# Soil_Moisture_Sensor.net
KiCad netlist of a schematic drawn in Altium Designer
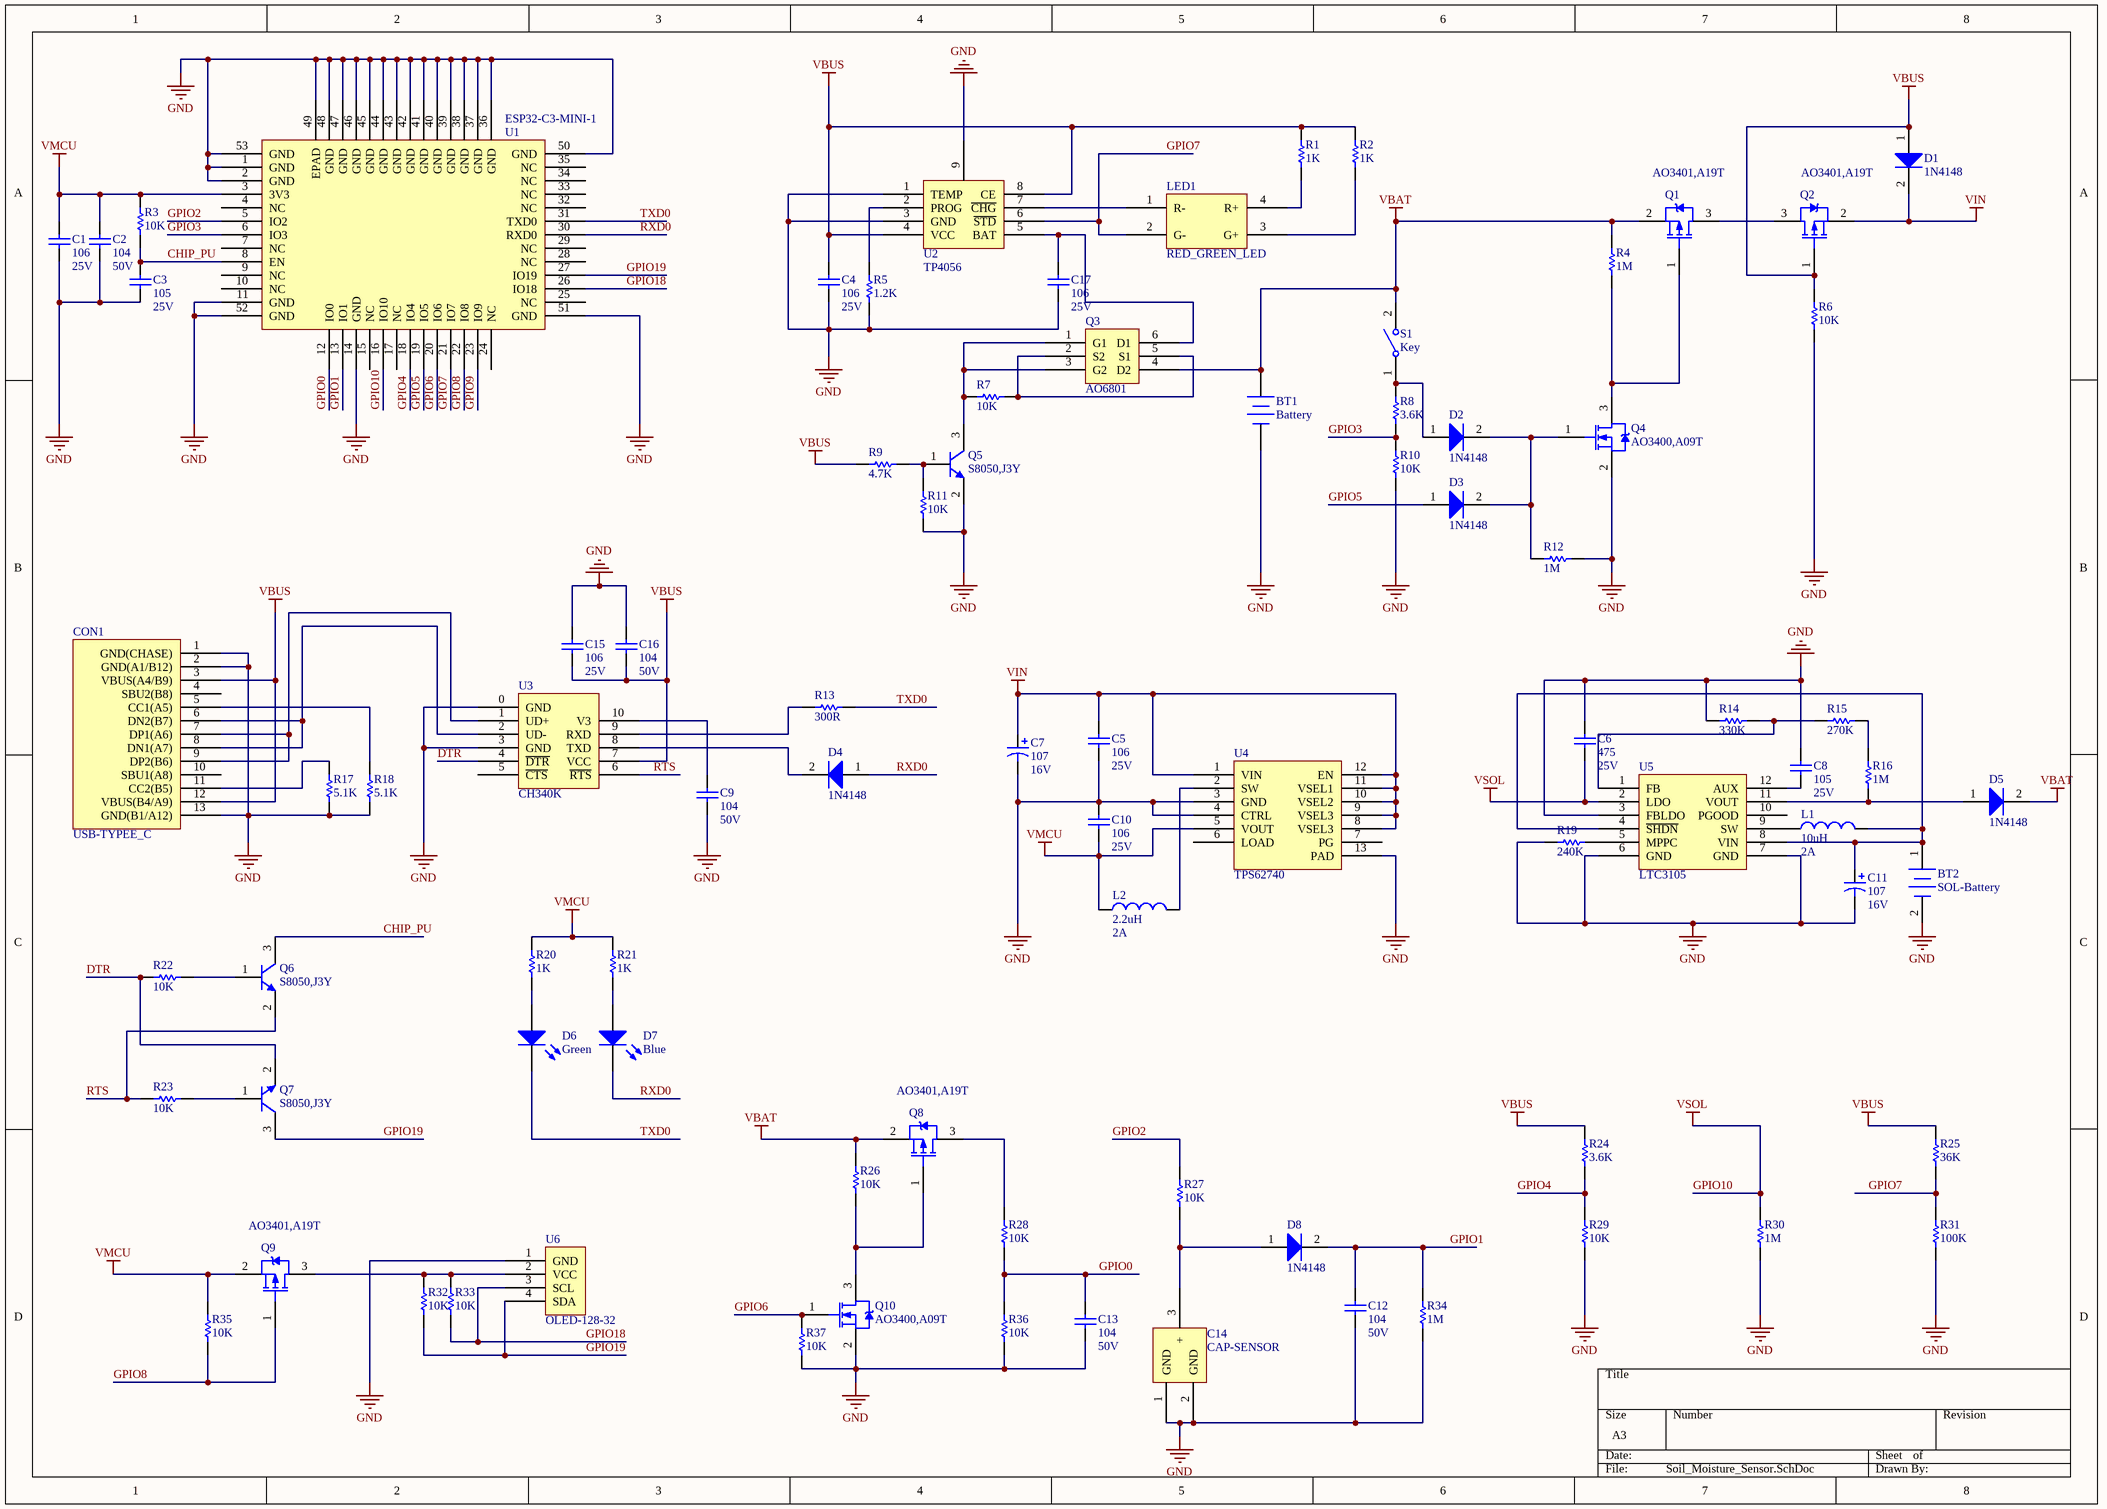
[diagram p0: Soil_Moisture_Sensor.SchDoc]

(export (version "E")
  (design (tool "Eeschema 10.0.6"))
  (components
    (comp (ref "BT1")
      (value "Battery")
      (footprint "Soil_Moisture_Sensor:BATTERY")
      (description "Multicell Battery")
      (fields (field (name "PUBLISHER") "Altium Limited"))
      (libsource (lib "") (part "Battery_1"))
    )
    (comp (ref "BT2")
      (value "SOL-Battery")
      (footprint "Soil_Moisture_Sensor:BATTERY-SOL")
      (description "Multicell Battery")
      (fields (field (name "PUBLISHER") "Altium Limited"))
      (libsource (lib "Miscellaneous Devices") (part "Battery"))
    )
    (comp (ref "C1")
      (value "25V")
      (footprint "Soil_Moisture_Sensor:CAPC1608L")
      (description "Capacitor")
      (fields (field (name "ALTIUM_VALUE") "106") (field (name "PUBLISHER") "Altium Limited"))
      (libsource (lib "Miscellaneous Devices") (part "Cap"))
    )
    (comp (ref "C2")
      (value "50V")
      (footprint "Soil_Moisture_Sensor:CAPC1608L")
      (description "Capacitor")
      (fields (field (name "ALTIUM_VALUE") "104") (field (name "PUBLISHER") "Altium Limited"))
      (libsource (lib "Miscellaneous Devices") (part "Cap"))
    )
    (comp (ref "C3")
      (value "25V")
      (footprint "Soil_Moisture_Sensor:CAPC1608L")
      (description "Capacitor")
      (fields (field (name "ALTIUM_VALUE") "105") (field (name "PUBLISHER") "Altium Limited"))
      (libsource (lib "Miscellaneous Devices") (part "Cap"))
    )
    (comp (ref "C4")
      (value "25V")
      (footprint "Soil_Moisture_Sensor:CAPC1608L")
      (description "Capacitor")
      (fields (field (name "ALTIUM_VALUE") "106") (field (name "PUBLISHER") "Altium Limited"))
      (libsource (lib "Miscellaneous Devices") (part "Cap"))
    )
    (comp (ref "C5")
      (value "25V")
      (footprint "Soil_Moisture_Sensor:CAPC1608L")
      (description "Capacitor")
      (fields (field (name "ALTIUM_VALUE") "106") (field (name "PUBLISHER") "Altium Limited"))
      (libsource (lib "Miscellaneous Devices") (part "Cap"))
    )
    (comp (ref "C6")
      (value "25V")
      (footprint "Soil_Moisture_Sensor:CAPC1608L")
      (description "Capacitor")
      (fields (field (name "ALTIUM_VALUE") "475") (field (name "PUBLISHER") "Altium Limited"))
      (libsource (lib "Miscellaneous Devices") (part "Cap"))
    )
    (comp (ref "C7")
      (value "16V")
      (footprint "Soil_Moisture_Sensor:TC6032-2412")
      (description "Polarized Capacitor (Radial)")
      (fields (field (name "ALTIUM_VALUE") "107") (field (name "PUBLISHER") "Altium Limited"))
      (libsource (lib "Miscellaneous Devices") (part "Cap Pol1"))
    )
    (comp (ref "C8")
      (value "25V")
      (footprint "Soil_Moisture_Sensor:CAPC1608L")
      (description "Capacitor")
      (fields (field (name "ALTIUM_VALUE") "105") (field (name "PUBLISHER") "Altium Limited"))
      (libsource (lib "Miscellaneous Devices") (part "Cap"))
    )
    (comp (ref "C9")
      (value "50V")
      (footprint "Soil_Moisture_Sensor:CAPC1608L")
      (description "Capacitor")
      (fields (field (name "ALTIUM_VALUE") "104") (field (name "PUBLISHER") "Altium Limited"))
      (libsource (lib "Miscellaneous Devices") (part "Cap"))
    )
    (comp (ref "C10")
      (value "25V")
      (footprint "Soil_Moisture_Sensor:CAPC1608L")
      (description "Capacitor")
      (fields (field (name "ALTIUM_VALUE") "106") (field (name "PUBLISHER") "Altium Limited"))
      (libsource (lib "Miscellaneous Devices") (part "Cap"))
    )
    (comp (ref "C11")
      (value "16V")
      (footprint "Soil_Moisture_Sensor:TC6032-2412")
      (description "Polarized Capacitor (Radial)")
      (fields (field (name "ALTIUM_VALUE") "107") (field (name "PUBLISHER") "Altium Limited"))
      (libsource (lib "Miscellaneous Devices") (part "Cap Pol1"))
    )
    (comp (ref "C12")
      (value "50V")
      (footprint "Soil_Moisture_Sensor:CAPC1608L")
      (description "Capacitor")
      (fields (field (name "ALTIUM_VALUE") "104") (field (name "PUBLISHER") "Altium Limited"))
      (libsource (lib "Miscellaneous Devices") (part "Cap"))
    )
    (comp (ref "C13")
      (value "50V")
      (footprint "Soil_Moisture_Sensor:CAPC1608L")
      (description "Capacitor")
      (fields (field (name "ALTIUM_VALUE") "104") (field (name "PUBLISHER") "Altium Limited"))
      (libsource (lib "Miscellaneous Devices") (part "Cap"))
    )
    (comp (ref "C14")
      (value "CAP-SENSOR")
      (footprint "CAP-SENSOR")
      (libsource (lib "Soil_Moisture_Sensor") (part "CAP-SENSOR"))
    )
    (comp (ref "C15")
      (value "25V")
      (footprint "Soil_Moisture_Sensor:CAPC1608L")
      (description "Capacitor")
      (fields (field (name "ALTIUM_VALUE") "106") (field (name "PUBLISHER") "Altium Limited"))
      (libsource (lib "Miscellaneous Devices") (part "Cap"))
    )
    (comp (ref "C16")
      (value "50V")
      (footprint "Soil_Moisture_Sensor:CAPC1608L")
      (description "Capacitor")
      (fields (field (name "ALTIUM_VALUE") "104") (field (name "PUBLISHER") "Altium Limited"))
      (libsource (lib "Miscellaneous Devices") (part "Cap"))
    )
    (comp (ref "C17")
      (value "25V")
      (footprint "Soil_Moisture_Sensor:CAPC1608L")
      (description "Capacitor")
      (fields (field (name "ALTIUM_VALUE") "106") (field (name "PUBLISHER") "Altium Limited"))
      (libsource (lib "Miscellaneous Devices") (part "Cap"))
    )
    (comp (ref "CON1")
      (value "USB-TYPEE_C")
      (footprint "Soil_Moisture_Sensor:USB-TYPE_C")
      (libsource (lib "Soil_Moisture_Sensor") (part "USB-TYPEE_C"))
    )
    (comp (ref "D1")
      (value "1N4148")
      (footprint "Soil_Moisture_Sensor:CD3216-1206")
      (description "Default Diode")
      (fields (field (name "PUBLISHER") "Altium Limited"))
      (libsource (lib "Miscellaneous Devices") (part "Diode"))
    )
    (comp (ref "D2")
      (value "1N4148")
      (footprint "Soil_Moisture_Sensor:CD3216-1206")
      (description "Default Diode")
      (fields (field (name "PUBLISHER") "Altium Limited"))
      (libsource (lib "Miscellaneous Devices") (part "Diode"))
    )
    (comp (ref "D3")
      (value "1N4148")
      (footprint "Soil_Moisture_Sensor:CD3216-1206")
      (description "Default Diode")
      (fields (field (name "PUBLISHER") "Altium Limited"))
      (libsource (lib "Miscellaneous Devices") (part "Diode"))
    )
    (comp (ref "D4")
      (value "1N4148")
      (footprint "Soil_Moisture_Sensor:CD3216-1206")
      (description "Default Diode")
      (fields (field (name "PUBLISHER") "Altium Limited"))
      (libsource (lib "Miscellaneous Devices") (part "Diode"))
    )
    (comp (ref "D5")
      (value "1N4148")
      (footprint "Soil_Moisture_Sensor:CD3216-1206")
      (description "Default Diode")
      (fields (field (name "PUBLISHER") "Altium Limited"))
      (libsource (lib "Miscellaneous Devices") (part "Diode"))
    )
    (comp (ref "D6")
      (value "Green")
      (footprint "Soil_Moisture_Sensor:CD1608-0603")
      (description "Typical INFRARED GaAs LED")
      (fields (field (name "PUBLISHER") "Altium Limited"))
      (libsource (lib "Miscellaneous Devices") (part "LED0"))
    )
    (comp (ref "D7")
      (value "Blue")
      (footprint "Soil_Moisture_Sensor:CD1608-0603")
      (description "Typical INFRARED GaAs LED")
      (fields (field (name "PUBLISHER") "Altium Limited"))
      (libsource (lib "Miscellaneous Devices") (part "LED0"))
    )
    (comp (ref "D8")
      (value "1N4148")
      (footprint "Soil_Moisture_Sensor:CD3216-1206")
      (description "Default Diode")
      (fields (field (name "PUBLISHER") "Altium Limited"))
      (libsource (lib "Miscellaneous Devices") (part "Diode"))
    )
    (comp (ref "L1")
      (value "2A")
      (footprint "Soil_Moisture_Sensor:INDC2520X06N")
      (description "Inductor")
      (fields (field (name "ALTIUM_VALUE") "10uH") (field (name "PUBLISHER") "Altium Limited"))
      (libsource (lib "Miscellaneous Devices") (part "Inductor"))
    )
    (comp (ref "L2")
      (value "2A")
      (footprint "Soil_Moisture_Sensor:INDC2520X06N")
      (description "Inductor")
      (fields (field (name "ALTIUM_VALUE") "2.2uH") (field (name "PUBLISHER") "Altium Limited"))
      (libsource (lib "Miscellaneous Devices") (part "Inductor"))
    )
    (comp (ref "LED1")
      (value "RED_GREEN_LED")
      (footprint "Soil_Moisture_Sensor:RED_GREEN_LED1206")
      (libsource (lib "Soil_Moisture_Sensor") (part "RED_GREEN_LED"))
    )
    (comp (ref "Q1")
      (value "AO3401,A19T")
      (footprint "Soil_Moisture_Sensor:SOT-23B_L")
      (description "P-Channel Power MOSFET")
      (fields (field (name "PUBLISHER") "Altium Limited"))
      (libsource (lib "Miscellaneous Devices") (part "PMOS-2"))
    )
    (comp (ref "Q2")
      (value "AO3401,A19T")
      (footprint "Soil_Moisture_Sensor:SOT-23B_L")
      (description "P-Channel Power MOSFET")
      (fields (field (name "PUBLISHER") "Altium Limited"))
      (libsource (lib "Miscellaneous Devices") (part "PMOS-2"))
    )
    (comp (ref "Q3")
      (value "AO6801")
      (footprint "Soil_Moisture_Sensor:SOT95P330-6M")
      (libsource (lib "FireFly") (part "AO6801"))
    )
    (comp (ref "Q4")
      (value "AO3400,A09T")
      (footprint "Soil_Moisture_Sensor:SOT-23B_L")
      (description "N-Channel Power MOSFET")
      (fields (field (name "PUBLISHER") "Altium Limited"))
      (libsource (lib "Miscellaneous Devices") (part "NMOS-2"))
    )
    (comp (ref "Q5")
      (value "S8050,J3Y")
      (footprint "Soil_Moisture_Sensor:SOT-23B_L")
      (description "NPN Bipolar Transistor")
      (fields (field (name "PUBLISHER") "Altium Limited"))
      (libsource (lib "Miscellaneous Devices") (part "NPN"))
    )
    (comp (ref "Q6")
      (value "S8050,J3Y")
      (footprint "Soil_Moisture_Sensor:SOT-23B_L")
      (description "NPN Bipolar Transistor")
      (fields (field (name "PUBLISHER") "Altium Limited"))
      (libsource (lib "Miscellaneous Devices") (part "NPN"))
    )
    (comp (ref "Q7")
      (value "S8050,J3Y")
      (footprint "Soil_Moisture_Sensor:SOT-23B_L")
      (description "NPN Bipolar Transistor")
      (fields (field (name "PUBLISHER") "Altium Limited"))
      (libsource (lib "Miscellaneous Devices") (part "NPN"))
    )
    (comp (ref "Q8")
      (value "AO3401,A19T")
      (footprint "Soil_Moisture_Sensor:SOT-23B_L")
      (description "P-Channel Power MOSFET")
      (fields (field (name "PUBLISHER") "Altium Limited"))
      (libsource (lib "Miscellaneous Devices") (part "PMOS-2"))
    )
    (comp (ref "Q9")
      (value "AO3401,A19T")
      (footprint "Soil_Moisture_Sensor:SOT-23B_L")
      (description "P-Channel Power MOSFET")
      (fields (field (name "PUBLISHER") "Altium Limited"))
      (libsource (lib "Miscellaneous Devices") (part "PMOS-2"))
    )
    (comp (ref "Q10")
      (value "AO3400,A09T")
      (footprint "Soil_Moisture_Sensor:SOT-23B_L")
      (description "N-Channel Power MOSFET")
      (fields (field (name "PUBLISHER") "Altium Limited"))
      (libsource (lib "Miscellaneous Devices") (part "NMOS-2"))
    )
    (comp (ref "R1")
      (value "1K")
      (footprint "Soil_Moisture_Sensor:RESC1608L")
      (description "Resistor")
      (fields (field (name "Comment") "Res1") (field (name "PUBLISHER") "Altium Limited"))
      (libsource (lib "Miscellaneous Devices") (part "Res1"))
    )
    (comp (ref "R2")
      (value "1K")
      (footprint "Soil_Moisture_Sensor:RESC1608L")
      (description "Resistor")
      (fields (field (name "Comment") "Res1") (field (name "PUBLISHER") "Altium Limited"))
      (libsource (lib "Miscellaneous Devices") (part "Res1"))
    )
    (comp (ref "R3")
      (value "10K")
      (footprint "Soil_Moisture_Sensor:RESC1608L")
      (description "Resistor")
      (fields (field (name "Comment") "Res1") (field (name "PUBLISHER") "Altium Limited"))
      (libsource (lib "Miscellaneous Devices") (part "Res1"))
    )
    (comp (ref "R4")
      (value "1M")
      (footprint "Soil_Moisture_Sensor:RESC1608L")
      (description "Resistor")
      (fields (field (name "Comment") "Res1") (field (name "PUBLISHER") "Altium Limited"))
      (libsource (lib "Miscellaneous Devices") (part "Res1"))
    )
    (comp (ref "R5")
      (value "1.2K")
      (footprint "Soil_Moisture_Sensor:RESC1608L")
      (description "Resistor")
      (fields (field (name "Comment") "Res1") (field (name "PUBLISHER") "Altium Limited"))
      (libsource (lib "Miscellaneous Devices") (part "Res1"))
    )
    (comp (ref "R6")
      (value "10K")
      (footprint "Soil_Moisture_Sensor:RESC1608L")
      (description "Resistor")
      (fields (field (name "Comment") "Res1") (field (name "PUBLISHER") "Altium Limited"))
      (libsource (lib "Miscellaneous Devices") (part "Res1"))
    )
    (comp (ref "R7")
      (value "10K")
      (footprint "Soil_Moisture_Sensor:RESC1608L")
      (description "Resistor")
      (fields (field (name "Comment") "Res1") (field (name "PUBLISHER") "Altium Limited"))
      (libsource (lib "Miscellaneous Devices") (part "Res1"))
    )
    (comp (ref "R8")
      (value "3.6K")
      (footprint "Soil_Moisture_Sensor:RESC1608L")
      (description "Resistor")
      (fields (field (name "Comment") "Res1") (field (name "PUBLISHER") "Altium Limited"))
      (libsource (lib "Miscellaneous Devices") (part "Res1"))
    )
    (comp (ref "R9")
      (value "4.7K")
      (footprint "Soil_Moisture_Sensor:RESC1608L")
      (description "Resistor")
      (fields (field (name "Comment") "Res1") (field (name "PUBLISHER") "Altium Limited"))
      (libsource (lib "Miscellaneous Devices") (part "Res1"))
    )
    (comp (ref "R10")
      (value "10K")
      (footprint "Soil_Moisture_Sensor:RESC1608L")
      (description "Resistor")
      (fields (field (name "Comment") "Res1") (field (name "PUBLISHER") "Altium Limited"))
      (libsource (lib "Miscellaneous Devices") (part "Res1"))
    )
    (comp (ref "R11")
      (value "10K")
      (footprint "Soil_Moisture_Sensor:RESC1608L")
      (description "Resistor")
      (fields (field (name "Comment") "Res1") (field (name "PUBLISHER") "Altium Limited"))
      (libsource (lib "Miscellaneous Devices") (part "Res1"))
    )
    (comp (ref "R12")
      (value "1M")
      (footprint "Soil_Moisture_Sensor:RESC1608L")
      (description "Resistor")
      (fields (field (name "Comment") "Res1") (field (name "PUBLISHER") "Altium Limited"))
      (libsource (lib "Miscellaneous Devices") (part "Res1"))
    )
    (comp (ref "R13")
      (value "300R")
      (footprint "Soil_Moisture_Sensor:RESC1608L")
      (description "Resistor")
      (fields (field (name "Comment") "Res1") (field (name "PUBLISHER") "Altium Limited"))
      (libsource (lib "Miscellaneous Devices") (part "Res1"))
    )
    (comp (ref "R14")
      (value "330K")
      (footprint "Soil_Moisture_Sensor:RESC1608L")
      (description "Resistor")
      (fields (field (name "Comment") "Res1") (field (name "PUBLISHER") "Altium Limited"))
      (libsource (lib "Miscellaneous Devices") (part "Res1"))
    )
    (comp (ref "R15")
      (value "270K")
      (footprint "Soil_Moisture_Sensor:RESC1608L")
      (description "Resistor")
      (fields (field (name "Comment") "Res1") (field (name "PUBLISHER") "Altium Limited"))
      (libsource (lib "Miscellaneous Devices") (part "Res1"))
    )
    (comp (ref "R16")
      (value "1M")
      (footprint "Soil_Moisture_Sensor:RESC1608L")
      (description "Resistor")
      (fields (field (name "Comment") "Res1") (field (name "PUBLISHER") "Altium Limited"))
      (libsource (lib "Miscellaneous Devices") (part "Res1"))
    )
    (comp (ref "R17")
      (value "5.1K")
      (footprint "Soil_Moisture_Sensor:RESC1608L")
      (description "Resistor")
      (fields (field (name "Comment") "Res1") (field (name "PUBLISHER") "Altium Limited"))
      (libsource (lib "Miscellaneous Devices") (part "Res1"))
    )
    (comp (ref "R18")
      (value "5.1K")
      (footprint "Soil_Moisture_Sensor:RESC1608L")
      (description "Resistor")
      (fields (field (name "Comment") "Res1") (field (name "PUBLISHER") "Altium Limited"))
      (libsource (lib "Miscellaneous Devices") (part "Res1"))
    )
    (comp (ref "R19")
      (value "240K")
      (footprint "Soil_Moisture_Sensor:RESC1608L")
      (description "Resistor")
      (fields (field (name "Comment") "Res1") (field (name "PUBLISHER") "Altium Limited"))
      (libsource (lib "Miscellaneous Devices") (part "Res1"))
    )
    (comp (ref "R20")
      (value "1K")
      (footprint "Soil_Moisture_Sensor:RESC1608L")
      (description "Resistor")
      (fields (field (name "Comment") "Res1") (field (name "PUBLISHER") "Altium Limited"))
      (libsource (lib "Miscellaneous Devices") (part "Res1"))
    )
    (comp (ref "R21")
      (value "1K")
      (footprint "Soil_Moisture_Sensor:RESC1608L")
      (description "Resistor")
      (fields (field (name "Comment") "Res1") (field (name "PUBLISHER") "Altium Limited"))
      (libsource (lib "Miscellaneous Devices") (part "Res1"))
    )
    (comp (ref "R22")
      (value "10K")
      (footprint "Soil_Moisture_Sensor:RESC1608L")
      (description "Resistor")
      (fields (field (name "Comment") "Res1") (field (name "PUBLISHER") "Altium Limited"))
      (libsource (lib "Miscellaneous Devices") (part "Res1"))
    )
    (comp (ref "R23")
      (value "10K")
      (footprint "Soil_Moisture_Sensor:RESC1608L")
      (description "Resistor")
      (fields (field (name "Comment") "Res1") (field (name "PUBLISHER") "Altium Limited"))
      (libsource (lib "Miscellaneous Devices") (part "Res1"))
    )
    (comp (ref "R24")
      (value "3.6K")
      (footprint "Soil_Moisture_Sensor:RESC1608L")
      (description "Resistor")
      (fields (field (name "Comment") "Res1") (field (name "PUBLISHER") "Altium Limited"))
      (libsource (lib "Miscellaneous Devices") (part "Res1"))
    )
    (comp (ref "R25")
      (value "36K")
      (footprint "Soil_Moisture_Sensor:RESC1608L")
      (description "Resistor")
      (fields (field (name "Comment") "Res1") (field (name "PUBLISHER") "Altium Limited"))
      (libsource (lib "Miscellaneous Devices") (part "Res1"))
    )
    (comp (ref "R26")
      (value "10K")
      (footprint "Soil_Moisture_Sensor:RESC1608L")
      (description "Resistor")
      (fields (field (name "Comment") "Res1") (field (name "PUBLISHER") "Altium Limited"))
      (libsource (lib "Miscellaneous Devices") (part "Res1"))
    )
    (comp (ref "R27")
      (value "10K")
      (footprint "Soil_Moisture_Sensor:RESC1608L")
      (description "Resistor")
      (fields (field (name "Comment") "Res1") (field (name "PUBLISHER") "Altium Limited"))
      (libsource (lib "Miscellaneous Devices") (part "Res1"))
    )
    (comp (ref "R28")
      (value "10K")
      (footprint "Soil_Moisture_Sensor:RESC1608L")
      (description "Resistor")
      (fields (field (name "Comment") "Res1") (field (name "PUBLISHER") "Altium Limited"))
      (libsource (lib "Miscellaneous Devices") (part "Res1"))
    )
    (comp (ref "R29")
      (value "10K")
      (footprint "Soil_Moisture_Sensor:RESC1608L")
      (description "Resistor")
      (fields (field (name "Comment") "Res1") (field (name "PUBLISHER") "Altium Limited"))
      (libsource (lib "Miscellaneous Devices") (part "Res1"))
    )
    (comp (ref "R30")
      (value "1M")
      (footprint "Soil_Moisture_Sensor:RESC1608L")
      (description "Resistor")
      (fields (field (name "Comment") "Res1") (field (name "PUBLISHER") "Altium Limited"))
      (libsource (lib "Miscellaneous Devices") (part "Res1"))
    )
    (comp (ref "R31")
      (value "100K")
      (footprint "Soil_Moisture_Sensor:RESC1608L")
      (description "Resistor")
      (fields (field (name "Comment") "Res1") (field (name "PUBLISHER") "Altium Limited"))
      (libsource (lib "Miscellaneous Devices") (part "Res1"))
    )
    (comp (ref "R32")
      (value "10K")
      (footprint "Soil_Moisture_Sensor:RESC1608L")
      (description "Resistor")
      (fields (field (name "Comment") "Res1") (field (name "PUBLISHER") "Altium Limited"))
      (libsource (lib "Miscellaneous Devices") (part "Res1"))
    )
    (comp (ref "R33")
      (value "10K")
      (footprint "Soil_Moisture_Sensor:RESC1608L")
      (description "Resistor")
      (fields (field (name "Comment") "Res1") (field (name "PUBLISHER") "Altium Limited"))
      (libsource (lib "Miscellaneous Devices") (part "Res1"))
    )
    (comp (ref "R34")
      (value "1M")
      (footprint "Soil_Moisture_Sensor:RESC1608L")
      (description "Resistor")
      (fields (field (name "Comment") "Res1") (field (name "PUBLISHER") "Altium Limited"))
      (libsource (lib "Miscellaneous Devices") (part "Res1"))
    )
    (comp (ref "R35")
      (value "10K")
      (footprint "Soil_Moisture_Sensor:RESC1608L")
      (description "Resistor")
      (fields (field (name "Comment") "Res1") (field (name "PUBLISHER") "Altium Limited"))
      (libsource (lib "Miscellaneous Devices") (part "Res1"))
    )
    (comp (ref "R36")
      (value "10K")
      (footprint "Soil_Moisture_Sensor:RESC1608L")
      (description "Resistor")
      (fields (field (name "Comment") "Res1") (field (name "PUBLISHER") "Altium Limited"))
      (libsource (lib "Miscellaneous Devices") (part "Res1"))
    )
    (comp (ref "R37")
      (value "10K")
      (footprint "Soil_Moisture_Sensor:RESC1608L")
      (description "Resistor")
      (fields (field (name "Comment") "Res1") (field (name "PUBLISHER") "Altium Limited"))
      (libsource (lib "Miscellaneous Devices") (part "Res1"))
    )
    (comp (ref "S1")
      (value "Key")
      (footprint "Soil_Moisture_Sensor:KEY")
      (description "Single-Pole, Single-Throw Switch")
      (fields (field (name "PUBLISHER") "Altium Limited"))
      (libsource (lib "Miscellaneous Devices") (part "SW-SPST"))
    )
    (comp (ref "U1")
      (value "ESP32-C3-MINI-1")
      (footprint "Soil_Moisture_Sensor:XCVR_ESP32-C3-MINI-1-N4")
      (libsource (lib "Soil_Moisture_Sensor") (part "ESP32-C3-MINI-1"))
    )
    (comp (ref "U2")
      (value "TP4056")
      (footprint "Soil_Moisture_Sensor:SOP127P780-8M")
      (libsource (lib "Soil_Moisture_Sensor") (part "TP4056"))
    )
    (comp (ref "U3")
      (value "CH340K")
      (footprint "Soil_Moisture_Sensor:ESOP100-10")
      (libsource (lib "Soil_Moisture_Sensor") (part "CH340K"))
    )
    (comp (ref "U4")
      (value "TPS62740")
      (footprint "Soil_Moisture_Sensor:DSS0012A")
      (libsource (lib "Soil_Moisture_Sensor") (part "TPS62740"))
    )
    (comp (ref "U5")
      (value "LTC3105")
      (footprint "Soil_Moisture_Sensor:TSOP65P490X110-12L")
      (libsource (lib "Soil_Moisture_Sensor") (part "LTC3105"))
    )
    (comp (ref "U6")
      (value "OLED-128-32")
      (footprint "OLED-128-32")
      (libsource (lib "Soil_Moisture_Sensor") (part "OLED-128-32"))
    )
  )
  (nets
    (net (code "1") (name "/CHIP_PU") (class "Default")
      (node (ref "C3") (pin "2") (pinfunction "2_2") (pintype "passive"))
      (node (ref "Q6") (pin "3") (pinfunction "C_3") (pintype "passive"))
      (node (ref "R3") (pin "1") (pinfunction "1_1") (pintype "passive"))
      (node (ref "U1") (pin "8") (pinfunction "EN_8") (pintype "passive"))
    )
    (net (code "2") (name "/DTR") (class "Default")
      (node (ref "Q7") (pin "2") (pinfunction "E_2") (pintype "passive"))
      (node (ref "R22") (pin "2") (pinfunction "2_2") (pintype "passive"))
      (node (ref "U3") (pin "4") (pinfunction "~{DTR}_4") (pintype "passive"))
    )
    (net (code "3") (name "/GPIO0") (class "Default")
      (node (ref "C13") (pin "2") (pinfunction "2_2") (pintype "passive"))
      (node (ref "R28") (pin "1") (pinfunction "1_1") (pintype "passive"))
      (node (ref "R36") (pin "2") (pinfunction "2_2") (pintype "passive"))
      (node (ref "U1") (pin "12") (pinfunction "IO0_12") (pintype "passive"))
    )
    (net (code "4") (name "/GPIO1") (class "Default")
      (node (ref "C12") (pin "2") (pinfunction "2_2") (pintype "passive"))
      (node (ref "D8") (pin "2") (pinfunction "K_2") (pintype "passive"))
      (node (ref "R34") (pin "2") (pinfunction "2_2") (pintype "passive"))
      (node (ref "U1") (pin "13") (pinfunction "IO1_13") (pintype "passive"))
    )
    (net (code "5") (name "/GPIO2") (class "Default")
      (node (ref "R27") (pin "2") (pinfunction "2_2") (pintype "passive"))
      (node (ref "U1") (pin "5") (pinfunction "IO2_5") (pintype "passive"))
    )
    (net (code "6") (name "/GPIO3") (class "Default")
      (node (ref "R10") (pin "2") (pinfunction "2_2") (pintype "passive"))
      (node (ref "R8") (pin "1") (pinfunction "1_1") (pintype "passive"))
      (node (ref "U1") (pin "6") (pinfunction "IO3_6") (pintype "passive"))
    )
    (net (code "7") (name "/GPIO4") (class "Default")
      (node (ref "R24") (pin "1") (pinfunction "1_1") (pintype "passive"))
      (node (ref "R29") (pin "2") (pinfunction "2_2") (pintype "passive"))
      (node (ref "U1") (pin "18") (pinfunction "IO4_18") (pintype "passive"))
    )
    (net (code "8") (name "/GPIO5") (class "Default")
      (node (ref "D3") (pin "1") (pinfunction "A_1") (pintype "passive"))
      (node (ref "U1") (pin "19") (pinfunction "IO5_19") (pintype "passive"))
    )
    (net (code "9") (name "/GPIO6") (class "Default")
      (node (ref "Q10") (pin "1") (pinfunction "G_1") (pintype "passive"))
      (node (ref "R37") (pin "2") (pinfunction "2_2") (pintype "passive"))
      (node (ref "U1") (pin "20") (pinfunction "IO6_20") (pintype "passive"))
    )
    (net (code "10") (name "/GPIO7") (class "Default")
      (node (ref "LED1") (pin "2") (pinfunction "G-_2") (pintype "passive"))
      (node (ref "R25") (pin "1") (pinfunction "1_1") (pintype "passive"))
      (node (ref "R31") (pin "2") (pinfunction "2_2") (pintype "passive"))
      (node (ref "U1") (pin "21") (pinfunction "IO7_21") (pintype "passive"))
      (node (ref "U2") (pin "6") (pinfunction "~{STD}_6") (pintype "passive"))
    )
    (net (code "11") (name "/GPIO8") (class "Default")
      (node (ref "Q9") (pin "1") (pinfunction "G_1") (pintype "passive"))
      (node (ref "R35") (pin "1") (pinfunction "1_1") (pintype "passive"))
      (node (ref "U1") (pin "22") (pinfunction "IO8_22") (pintype "passive"))
    )
    (net (code "12") (name "/GPIO9") (class "Default")
      (node (ref "U1") (pin "23") (pinfunction "IO9_23") (pintype "passive"))
    )
    (net (code "13") (name "/GPIO18") (class "Default")
      (node (ref "R33") (pin "2") (pinfunction "2_2") (pintype "passive"))
      (node (ref "U1") (pin "26") (pinfunction "IO18_26") (pintype "passive"))
      (node (ref "U6") (pin "3") (pinfunction "SCL_3") (pintype "passive"))
    )
    (net (code "14") (name "/GPIO19") (class "Default")
      (node (ref "Q7") (pin "3") (pinfunction "C_3") (pintype "passive"))
      (node (ref "R32") (pin "2") (pinfunction "2_2") (pintype "passive"))
      (node (ref "U1") (pin "27") (pinfunction "IO19_27") (pintype "passive"))
      (node (ref "U6") (pin "4") (pinfunction "SDA_4") (pintype "passive"))
    )
    (net (code "15") (name "/RTS") (class "Default")
      (node (ref "Q6") (pin "2") (pinfunction "E_2") (pintype "passive"))
      (node (ref "R23") (pin "2") (pinfunction "2_2") (pintype "passive"))
      (node (ref "U3") (pin "6") (pinfunction "~{RTS}_6") (pintype "passive"))
    )
    (net (code "16") (name "/RXD0") (class "Default")
      (node (ref "D4") (pin "1") (pinfunction "A_1") (pintype "passive"))
      (node (ref "D7") (pin "2") (pinfunction "K_2") (pintype "passive"))
      (node (ref "U1") (pin "30") (pinfunction "RXD0_30") (pintype "passive"))
    )
    (net (code "17") (name "/TXD0") (class "Default")
      (node (ref "D6") (pin "2") (pinfunction "K_2") (pintype "passive"))
      (node (ref "R13") (pin "1") (pinfunction "1_1") (pintype "passive"))
      (node (ref "U1") (pin "31") (pinfunction "TXD0_31") (pintype "passive"))
    )
    (net (code "18") (name "GND") (class "Default")
      (node (ref "BT1") (pin "2") (pinfunction "-_2") (pintype "passive"))
      (node (ref "BT2") (pin "2") (pinfunction "-_2") (pintype "passive"))
      (node (ref "C1") (pin "1") (pinfunction "1_1") (pintype "passive"))
      (node (ref "C10") (pin "2") (pinfunction "2_2") (pintype "passive"))
      (node (ref "C11") (pin "2") (pinfunction "2_2") (pintype "passive"))
      (node (ref "C12") (pin "1") (pinfunction "1_1") (pintype "passive"))
      (node (ref "C13") (pin "1") (pinfunction "1_1") (pintype "passive"))
      (node (ref "C14") (pin "1") (pinfunction "GND_1") (pintype "passive"))
      (node (ref "C14") (pin "2") (pinfunction "GND_2") (pintype "passive"))
      (node (ref "C15") (pin "2") (pinfunction "2_2") (pintype "passive"))
      (node (ref "C16") (pin "2") (pinfunction "2_2") (pintype "passive"))
      (node (ref "C17") (pin "1") (pinfunction "1_1") (pintype "passive"))
      (node (ref "C2") (pin "1") (pinfunction "1_1") (pintype "passive"))
      (node (ref "C3") (pin "1") (pinfunction "1_1") (pintype "passive"))
      (node (ref "C4") (pin "1") (pinfunction "1_1") (pintype "passive"))
      (node (ref "C5") (pin "1") (pinfunction "1_1") (pintype "passive"))
      (node (ref "C6") (pin "2") (pinfunction "2_2") (pintype "passive"))
      (node (ref "C7") (pin "2") (pinfunction "2_2") (pintype "passive"))
      (node (ref "C8") (pin "2") (pinfunction "2_2") (pintype "passive"))
      (node (ref "C9") (pin "1") (pinfunction "1_1") (pintype "passive"))
      (node (ref "CON1") (pin "1") (pinfunction "GND(CHASE)_1") (pintype "passive"))
      (node (ref "CON1") (pin "13") (pinfunction "GND(B1/A12)_13") (pintype "passive"))
      (node (ref "CON1") (pin "2") (pinfunction "GND(A1/B12)_2") (pintype "passive"))
      (node (ref "Q10") (pin "2") (pinfunction "S_2") (pintype "passive"))
      (node (ref "Q4") (pin "2") (pinfunction "S_2") (pintype "passive"))
      (node (ref "Q5") (pin "2") (pinfunction "E_2") (pintype "passive"))
      (node (ref "R10") (pin "1") (pinfunction "1_1") (pintype "passive"))
      (node (ref "R11") (pin "2") (pinfunction "2_2") (pintype "passive"))
      (node (ref "R12") (pin "1") (pinfunction "1_1") (pintype "passive"))
      (node (ref "R14") (pin "2") (pinfunction "2_2") (pintype "passive"))
      (node (ref "R17") (pin "1") (pinfunction "1_1") (pintype "passive"))
      (node (ref "R18") (pin "1") (pinfunction "1_1") (pintype "passive"))
      (node (ref "R19") (pin "1") (pinfunction "1_1") (pintype "passive"))
      (node (ref "R29") (pin "1") (pinfunction "1_1") (pintype "passive"))
      (node (ref "R30") (pin "1") (pinfunction "1_1") (pintype "passive"))
      (node (ref "R31") (pin "1") (pinfunction "1_1") (pintype "passive"))
      (node (ref "R34") (pin "1") (pinfunction "1_1") (pintype "passive"))
      (node (ref "R36") (pin "1") (pinfunction "1_1") (pintype "passive"))
      (node (ref "R37") (pin "1") (pinfunction "1_1") (pintype "passive"))
      (node (ref "R5") (pin "1") (pinfunction "1_1") (pintype "passive"))
      (node (ref "R6") (pin "1") (pinfunction "1_1") (pintype "passive"))
      (node (ref "U1") (pin "1") (pinfunction "GND_1") (pintype "passive"))
      (node (ref "U1") (pin "11") (pinfunction "GND_11") (pintype "passive"))
      (node (ref "U1") (pin "14") (pinfunction "GND_14") (pintype "passive"))
      (node (ref "U1") (pin "2") (pinfunction "GND_2") (pintype "passive"))
      (node (ref "U1") (pin "36") (pinfunction "GND_36") (pintype "passive"))
      (node (ref "U1") (pin "37") (pinfunction "GND_37") (pintype "passive"))
      (node (ref "U1") (pin "38") (pinfunction "GND_38") (pintype "passive"))
      (node (ref "U1") (pin "39") (pinfunction "GND_39") (pintype "passive"))
      (node (ref "U1") (pin "40") (pinfunction "GND_40") (pintype "passive"))
      (node (ref "U1") (pin "41") (pinfunction "GND_41") (pintype "passive"))
      (node (ref "U1") (pin "42") (pinfunction "GND_42") (pintype "passive"))
      (node (ref "U1") (pin "43") (pinfunction "GND_43") (pintype "passive"))
      (node (ref "U1") (pin "44") (pinfunction "GND_44") (pintype "passive"))
      (node (ref "U1") (pin "45") (pinfunction "GND_45") (pintype "passive"))
      (node (ref "U1") (pin "46") (pinfunction "GND_46") (pintype "passive"))
      (node (ref "U1") (pin "47") (pinfunction "GND_47") (pintype "passive"))
      (node (ref "U1") (pin "48") (pinfunction "GND_48") (pintype "passive"))
      (node (ref "U1") (pin "49") (pinfunction "EPAD_49") (pintype "passive"))
      (node (ref "U1") (pin "50") (pinfunction "GND_50") (pintype "passive"))
      (node (ref "U1") (pin "51") (pinfunction "GND_51") (pintype "passive"))
      (node (ref "U1") (pin "52") (pinfunction "GND_52") (pintype "passive"))
      (node (ref "U1") (pin "53") (pinfunction "GND_53") (pintype "passive"))
      (node (ref "U2") (pin "1") (pinfunction "TEMP_1") (pintype "passive"))
      (node (ref "U2") (pin "3") (pinfunction "GND_3") (pintype "passive"))
      (node (ref "U2") (pin "9") (pinfunction "9_9") (pintype "passive"))
      (node (ref "U3") (pin "0") (pinfunction "GND_0") (pintype "passive"))
      (node (ref "U3") (pin "3") (pinfunction "GND_3") (pintype "passive"))
      (node (ref "U4") (pin "13") (pinfunction "PAD_13") (pintype "passive"))
      (node (ref "U4") (pin "3") (pinfunction "GND_3") (pintype "passive"))
      (node (ref "U4") (pin "4") (pinfunction "CTRL_4") (pintype "passive"))
      (node (ref "U5") (pin "3") (pinfunction "FBLDO_3") (pintype "passive"))
      (node (ref "U5") (pin "6") (pinfunction "GND_6") (pintype "passive"))
      (node (ref "U5") (pin "7") (pinfunction "GND_7") (pintype "passive"))
      (node (ref "U6") (pin "1") (pinfunction "GND_1") (pintype "passive"))
    )
    (net (code "19") (name "Net-(BT2-+)") (class "Default")
      (node (ref "BT2") (pin "1") (pinfunction "+_1") (pintype "passive"))
      (node (ref "C11") (pin "1") (pinfunction "1_1") (pintype "passive"))
      (node (ref "L1") (pin "2") (pinfunction "2_2") (pintype "passive"))
      (node (ref "U5") (pin "4") (pinfunction "~{SHDN}_4") (pintype "passive"))
      (node (ref "U5") (pin "8") (pinfunction "VIN_8") (pintype "passive"))
    )
    (net (code "20") (name "Net-(C14-+)") (class "Default")
      (node (ref "C14") (pin "3") (pinfunction "+_3") (pintype "passive"))
      (node (ref "D8") (pin "1") (pinfunction "A_1") (pintype "passive"))
      (node (ref "R27") (pin "1") (pinfunction "1_1") (pintype "passive"))
    )
    (net (code "21") (name "Net-(CON1-CC1(A5))") (class "Default")
      (node (ref "CON1") (pin "5") (pinfunction "CC1(A5)_5") (pintype "passive"))
      (node (ref "R18") (pin "2") (pinfunction "2_2") (pintype "passive"))
    )
    (net (code "22") (name "Net-(CON1-CC2(B5))") (class "Default")
      (node (ref "CON1") (pin "11") (pinfunction "CC2(B5)_11") (pintype "passive"))
      (node (ref "R17") (pin "2") (pinfunction "2_2") (pintype "passive"))
    )
    (net (code "23") (name "Net-(CON1-DN1(A7))") (class "Default")
      (node (ref "CON1") (pin "6") (pinfunction "DN2(B7)_6") (pintype "passive"))
      (node (ref "CON1") (pin "8") (pinfunction "DN1(A7)_8") (pintype "passive"))
      (node (ref "U3") (pin "2") (pinfunction "UD-_2") (pintype "passive"))
    )
    (net (code "24") (name "Net-(CON1-DP1(A6))") (class "Default")
      (node (ref "CON1") (pin "7") (pinfunction "DP1(A6)_7") (pintype "passive"))
      (node (ref "CON1") (pin "9") (pinfunction "DP2(B6)_9") (pintype "passive"))
      (node (ref "U3") (pin "1") (pinfunction "UD+_1") (pintype "passive"))
    )
    (net (code "25") (name "Net-(D2-A)") (class "Default")
      (node (ref "D2") (pin "1") (pinfunction "A_1") (pintype "passive"))
      (node (ref "R8") (pin "2") (pinfunction "2_2") (pintype "passive"))
      (node (ref "S1") (pin "1") (pinfunction "COMMON_1") (pintype "passive"))
    )
    (net (code "26") (name "Net-(D2-K)") (class "Default")
      (node (ref "D2") (pin "2") (pinfunction "K_2") (pintype "passive"))
      (node (ref "D3") (pin "2") (pinfunction "K_2") (pintype "passive"))
      (node (ref "Q4") (pin "1") (pinfunction "G_1") (pintype "passive"))
      (node (ref "R12") (pin "2") (pinfunction "2_2") (pintype "passive"))
    )
    (net (code "27") (name "Net-(D4-K)") (class "Default")
      (node (ref "D4") (pin "2") (pinfunction "K_2") (pintype "passive"))
      (node (ref "U3") (pin "8") (pinfunction "TXD_8") (pintype "passive"))
    )
    (net (code "28") (name "Net-(D5-A)") (class "Default")
      (node (ref "D5") (pin "1") (pinfunction "A_1") (pintype "passive"))
      (node (ref "R16") (pin "2") (pinfunction "2_2") (pintype "passive"))
      (node (ref "U5") (pin "11") (pinfunction "VOUT_11") (pintype "passive"))
    )
    (net (code "29") (name "Net-(D6-A)") (class "Default")
      (node (ref "D6") (pin "1") (pinfunction "A_1") (pintype "passive"))
      (node (ref "R20") (pin "2") (pinfunction "2_2") (pintype "passive"))
    )
    (net (code "30") (name "Net-(D7-A)") (class "Default")
      (node (ref "D7") (pin "1") (pinfunction "A_1") (pintype "passive"))
      (node (ref "R21") (pin "2") (pinfunction "2_2") (pintype "passive"))
    )
    (net (code "31") (name "Net-(LED1-G+)") (class "Default")
      (node (ref "LED1") (pin "3") (pinfunction "G+_3") (pintype "passive"))
      (node (ref "R2") (pin "1") (pinfunction "1_1") (pintype "passive"))
    )
    (net (code "32") (name "Net-(LED1-R+)") (class "Default")
      (node (ref "LED1") (pin "4") (pinfunction "R+_4") (pintype "passive"))
      (node (ref "R1") (pin "1") (pinfunction "1_1") (pintype "passive"))
    )
    (net (code "33") (name "Net-(LED1-R-)") (class "Default")
      (node (ref "LED1") (pin "1") (pinfunction "R-_1") (pintype "passive"))
      (node (ref "U2") (pin "7") (pinfunction "~{CHG}_7") (pintype "passive"))
    )
    (net (code "34") (name "Net-(Q1-D)") (class "Default")
      (node (ref "Q1") (pin "3") (pinfunction "D_3") (pintype "passive"))
      (node (ref "Q2") (pin "3") (pinfunction "D_3") (pintype "passive"))
    )
    (net (code "35") (name "Net-(Q1-G)") (class "Default")
      (node (ref "Q1") (pin "1") (pinfunction "G_1") (pintype "passive"))
      (node (ref "Q4") (pin "3") (pinfunction "D_3") (pintype "passive"))
      (node (ref "R4") (pin "1") (pinfunction "1_1") (pintype "passive"))
    )
    (net (code "36") (name "Net-(Q3-D1)") (class "Default")
      (node (ref "C17") (pin "2") (pinfunction "2_2") (pintype "passive"))
      (node (ref "Q3") (pin "6") (pinfunction "D1_6") (pintype "passive"))
      (node (ref "U2") (pin "5") (pinfunction "BAT_5") (pintype "passive"))
    )
    (net (code "37") (name "Net-(Q3-G1)") (class "Default")
      (node (ref "Q3") (pin "1") (pinfunction "G1_1") (pintype "passive"))
      (node (ref "Q3") (pin "3") (pinfunction "G2_3") (pintype "passive"))
      (node (ref "Q5") (pin "3") (pinfunction "C_3") (pintype "passive"))
      (node (ref "R7") (pin "2") (pinfunction "2_2") (pintype "passive"))
    )
    (net (code "38") (name "Net-(Q3-S1)") (class "Default")
      (node (ref "Q3") (pin "2") (pinfunction "S2_2") (pintype "passive"))
      (node (ref "Q3") (pin "5") (pinfunction "S1_5") (pintype "passive"))
      (node (ref "R7") (pin "1") (pinfunction "1_1") (pintype "passive"))
    )
    (net (code "39") (name "Net-(Q5-B)") (class "Default")
      (node (ref "Q5") (pin "1") (pinfunction "B_1") (pintype "passive"))
      (node (ref "R11") (pin "1") (pinfunction "1_1") (pintype "passive"))
      (node (ref "R9") (pin "1") (pinfunction "1_1") (pintype "passive"))
    )
    (net (code "40") (name "Net-(Q6-B)") (class "Default")
      (node (ref "Q6") (pin "1") (pinfunction "B_1") (pintype "passive"))
      (node (ref "R22") (pin "1") (pinfunction "1_1") (pintype "passive"))
    )
    (net (code "41") (name "Net-(Q7-B)") (class "Default")
      (node (ref "Q7") (pin "1") (pinfunction "B_1") (pintype "passive"))
      (node (ref "R23") (pin "1") (pinfunction "1_1") (pintype "passive"))
    )
    (net (code "42") (name "Net-(Q8-D)") (class "Default")
      (node (ref "Q8") (pin "3") (pinfunction "D_3") (pintype "passive"))
      (node (ref "R28") (pin "2") (pinfunction "2_2") (pintype "passive"))
    )
    (net (code "43") (name "Net-(Q9-D)") (class "Default")
      (node (ref "Q9") (pin "3") (pinfunction "D_3") (pintype "passive"))
      (node (ref "R32") (pin "1") (pinfunction "1_1") (pintype "passive"))
      (node (ref "R33") (pin "1") (pinfunction "1_1") (pintype "passive"))
      (node (ref "U6") (pin "2") (pinfunction "VCC_2") (pintype "passive"))
    )
    (net (code "44") (name "Net-(Q10-D)") (class "Default")
      (node (ref "Q10") (pin "3") (pinfunction "D_3") (pintype "passive"))
      (node (ref "Q8") (pin "1") (pinfunction "G_1") (pintype "passive"))
      (node (ref "R26") (pin "1") (pinfunction "1_1") (pintype "passive"))
    )
    (net (code "45") (name "Net-(R15-Pad2)") (class "Default")
      (node (ref "R15") (pin "2") (pinfunction "2_2") (pintype "passive"))
      (node (ref "R16") (pin "1") (pinfunction "1_1") (pintype "passive"))
    )
    (net (code "46") (name "Net-(U2-PROG)") (class "Default")
      (node (ref "R5") (pin "2") (pinfunction "2_2") (pintype "passive"))
      (node (ref "U2") (pin "2") (pinfunction "PROG_2") (pintype "passive"))
    )
    (net (code "47") (name "Net-(U3-RXD)") (class "Default")
      (node (ref "R13") (pin "2") (pinfunction "2_2") (pintype "passive"))
      (node (ref "U3") (pin "9") (pinfunction "RXD_9") (pintype "passive"))
    )
    (net (code "48") (name "Net-(U3-V3)") (class "Default")
      (node (ref "C9") (pin "2") (pinfunction "2_2") (pintype "passive"))
      (node (ref "U3") (pin "10") (pinfunction "V3_10") (pintype "passive"))
    )
    (net (code "49") (name "Net-(U4-SW)") (class "Default")
      (node (ref "L2") (pin "2") (pinfunction "2_2") (pintype "passive"))
      (node (ref "U4") (pin "2") (pinfunction "SW_2") (pintype "passive"))
    )
    (net (code "50") (name "Net-(U5-AUX)") (class "Default")
      (node (ref "C8") (pin "1") (pinfunction "1_1") (pintype "passive"))
      (node (ref "U5") (pin "12") (pinfunction "AUX_12") (pintype "passive"))
    )
    (net (code "51") (name "Net-(U5-FB)") (class "Default")
      (node (ref "R14") (pin "1") (pinfunction "1_1") (pintype "passive"))
      (node (ref "R15") (pin "1") (pinfunction "1_1") (pintype "passive"))
      (node (ref "U5") (pin "1") (pinfunction "FB_1") (pintype "passive"))
    )
    (net (code "52") (name "Net-(U5-MPPC)") (class "Default")
      (node (ref "R19") (pin "2") (pinfunction "2_2") (pintype "passive"))
      (node (ref "U5") (pin "5") (pinfunction "MPPC_5") (pintype "passive"))
    )
    (net (code "53") (name "Net-(U5-SW)") (class "Default")
      (node (ref "L1") (pin "1") (pinfunction "1_1") (pintype "passive"))
      (node (ref "U5") (pin "9") (pinfunction "SW_9") (pintype "passive"))
    )
    (net (code "54") (name "VBAT") (class "Default")
      (node (ref "BT1") (pin "1") (pinfunction "+_1") (pintype "passive"))
      (node (ref "D5") (pin "2") (pinfunction "K_2") (pintype "passive"))
      (node (ref "Q1") (pin "2") (pinfunction "S_2") (pintype "passive"))
      (node (ref "Q3") (pin "4") (pinfunction "D2_4") (pintype "passive"))
      (node (ref "Q8") (pin "2") (pinfunction "S_2") (pintype "passive"))
      (node (ref "R26") (pin "2") (pinfunction "2_2") (pintype "passive"))
      (node (ref "R4") (pin "2") (pinfunction "2_2") (pintype "passive"))
      (node (ref "S1") (pin "2") (pinfunction "NO_2") (pintype "passive"))
    )
    (net (code "55") (name "VBUS") (class "Default")
      (node (ref "C15") (pin "1") (pinfunction "1_1") (pintype "passive"))
      (node (ref "C16") (pin "1") (pinfunction "1_1") (pintype "passive"))
      (node (ref "C4") (pin "2") (pinfunction "2_2") (pintype "passive"))
      (node (ref "CON1") (pin "12") (pinfunction "VBUS(B4/A9)_12") (pintype "passive"))
      (node (ref "CON1") (pin "3") (pinfunction "VBUS(A4/B9)_3") (pintype "passive"))
      (node (ref "D1") (pin "1") (pinfunction "A_1") (pintype "passive"))
      (node (ref "Q2") (pin "1") (pinfunction "G_1") (pintype "passive"))
      (node (ref "R1") (pin "2") (pinfunction "2_2") (pintype "passive"))
      (node (ref "R2") (pin "2") (pinfunction "2_2") (pintype "passive"))
      (node (ref "R24") (pin "2") (pinfunction "2_2") (pintype "passive"))
      (node (ref "R25") (pin "2") (pinfunction "2_2") (pintype "passive"))
      (node (ref "R6") (pin "2") (pinfunction "2_2") (pintype "passive"))
      (node (ref "R9") (pin "2") (pinfunction "2_2") (pintype "passive"))
      (node (ref "U2") (pin "4") (pinfunction "VCC_4") (pintype "passive"))
      (node (ref "U2") (pin "8") (pinfunction "CE_8") (pintype "passive"))
      (node (ref "U3") (pin "7") (pinfunction "VCC_7") (pintype "passive"))
    )
    (net (code "56") (name "VIN") (class "Default")
      (node (ref "C5") (pin "2") (pinfunction "2_2") (pintype "passive"))
      (node (ref "C7") (pin "1") (pinfunction "1_1") (pintype "passive"))
      (node (ref "D1") (pin "2") (pinfunction "K_2") (pintype "passive"))
      (node (ref "Q2") (pin "2") (pinfunction "S_2") (pintype "passive"))
      (node (ref "U4") (pin "1") (pinfunction "VIN_1") (pintype "passive"))
      (node (ref "U4") (pin "10") (pinfunction "VSEL2_10") (pintype "passive"))
      (node (ref "U4") (pin "11") (pinfunction "VSEL1_11") (pintype "passive"))
      (node (ref "U4") (pin "12") (pinfunction "EN_12") (pintype "passive"))
      (node (ref "U4") (pin "8") (pinfunction "VSEL3_8") (pintype "passive"))
      (node (ref "U4") (pin "9") (pinfunction "VSEL3_9") (pintype "passive"))
    )
    (net (code "57") (name "VMCU") (class "Default")
      (node (ref "C1") (pin "2") (pinfunction "2_2") (pintype "passive"))
      (node (ref "C10") (pin "1") (pinfunction "1_1") (pintype "passive"))
      (node (ref "C2") (pin "2") (pinfunction "2_2") (pintype "passive"))
      (node (ref "L2") (pin "1") (pinfunction "1_1") (pintype "passive"))
      (node (ref "Q9") (pin "2") (pinfunction "S_2") (pintype "passive"))
      (node (ref "R20") (pin "1") (pinfunction "1_1") (pintype "passive"))
      (node (ref "R21") (pin "1") (pinfunction "1_1") (pintype "passive"))
      (node (ref "R3") (pin "2") (pinfunction "2_2") (pintype "passive"))
      (node (ref "R35") (pin "2") (pinfunction "2_2") (pintype "passive"))
      (node (ref "U1") (pin "3") (pinfunction "3V3_3") (pintype "passive"))
      (node (ref "U4") (pin "5") (pinfunction "VOUT_5") (pintype "passive"))
    )
    (net (code "58") (name "VSOL") (class "Default")
      (node (ref "C6") (pin "1") (pinfunction "1_1") (pintype "passive"))
      (node (ref "R30") (pin "2") (pinfunction "2_2") (pintype "passive"))
      (node (ref "U1") (pin "16") (pinfunction "IO10_16") (pintype "passive"))
      (node (ref "U5") (pin "2") (pinfunction "LDO_2") (pintype "passive"))
    )
    (net (code "59") (name "unconnected-(CON1-SBU1(A8)-Pad10)") (class "Default")
      (node (ref "CON1") (pin "10") (pinfunction "SBU1(A8)_10") (pintype "passive"))
    )
    (net (code "60") (name "unconnected-(CON1-SBU2(B8)-Pad4)") (class "Default")
      (node (ref "CON1") (pin "4") (pinfunction "SBU2(B8)_4") (pintype "passive"))
    )
    (net (code "61") (name "unconnected-(U1-NC-Pad4)") (class "Default")
      (node (ref "U1") (pin "4") (pinfunction "NC_4") (pintype "passive"))
    )
    (net (code "62") (name "unconnected-(U1-NC-Pad7)") (class "Default")
      (node (ref "U1") (pin "7") (pinfunction "NC_7") (pintype "passive"))
    )
    (net (code "63") (name "unconnected-(U1-NC-Pad9)") (class "Default")
      (node (ref "U1") (pin "9") (pinfunction "NC_9") (pintype "passive"))
    )
    (net (code "64") (name "unconnected-(U1-NC-Pad10)") (class "Default")
      (node (ref "U1") (pin "10") (pinfunction "NC_10") (pintype "passive"))
    )
    (net (code "65") (name "unconnected-(U1-NC-Pad15)") (class "Default")
      (node (ref "U1") (pin "15") (pinfunction "NC_15") (pintype "passive"))
    )
    (net (code "66") (name "unconnected-(U1-NC-Pad17)") (class "Default")
      (node (ref "U1") (pin "17") (pinfunction "NC_17") (pintype "passive"))
    )
    (net (code "67") (name "unconnected-(U1-NC-Pad24)") (class "Default")
      (node (ref "U1") (pin "24") (pinfunction "NC_24") (pintype "passive"))
    )
    (net (code "68") (name "unconnected-(U1-NC-Pad25)") (class "Default")
      (node (ref "U1") (pin "25") (pinfunction "NC_25") (pintype "passive"))
    )
    (net (code "69") (name "unconnected-(U1-NC-Pad28)") (class "Default")
      (node (ref "U1") (pin "28") (pinfunction "NC_28") (pintype "passive"))
    )
    (net (code "70") (name "unconnected-(U1-NC-Pad29)") (class "Default")
      (node (ref "U1") (pin "29") (pinfunction "NC_29") (pintype "passive"))
    )
    (net (code "71") (name "unconnected-(U1-NC-Pad32)") (class "Default")
      (node (ref "U1") (pin "32") (pinfunction "NC_32") (pintype "passive"))
    )
    (net (code "72") (name "unconnected-(U1-NC-Pad33)") (class "Default")
      (node (ref "U1") (pin "33") (pinfunction "NC_33") (pintype "passive"))
    )
    (net (code "73") (name "unconnected-(U1-NC-Pad34)") (class "Default")
      (node (ref "U1") (pin "34") (pinfunction "NC_34") (pintype "passive"))
    )
    (net (code "74") (name "unconnected-(U1-NC-Pad35)") (class "Default")
      (node (ref "U1") (pin "35") (pinfunction "NC_35") (pintype "passive"))
    )
    (net (code "75") (name "unconnected-(U3-~{CTS}-Pad5)") (class "Default")
      (node (ref "U3") (pin "5") (pinfunction "~{CTS}_5") (pintype "passive"))
    )
    (net (code "76") (name "unconnected-(U4-LOAD-Pad6)") (class "Default")
      (node (ref "U4") (pin "6") (pinfunction "LOAD_6") (pintype "passive"))
    )
    (net (code "77") (name "unconnected-(U4-PG-Pad7)") (class "Default")
      (node (ref "U4") (pin "7") (pinfunction "PG_7") (pintype "passive"))
    )
    (net (code "78") (name "unconnected-(U5-PGOOD-Pad10)") (class "Default")
      (node (ref "U5") (pin "10") (pinfunction "PGOOD_10") (pintype "passive"))
    )
  )
)
